# cougar_adapter.net
KiCad netlist of a schematic drawn in EAGLE
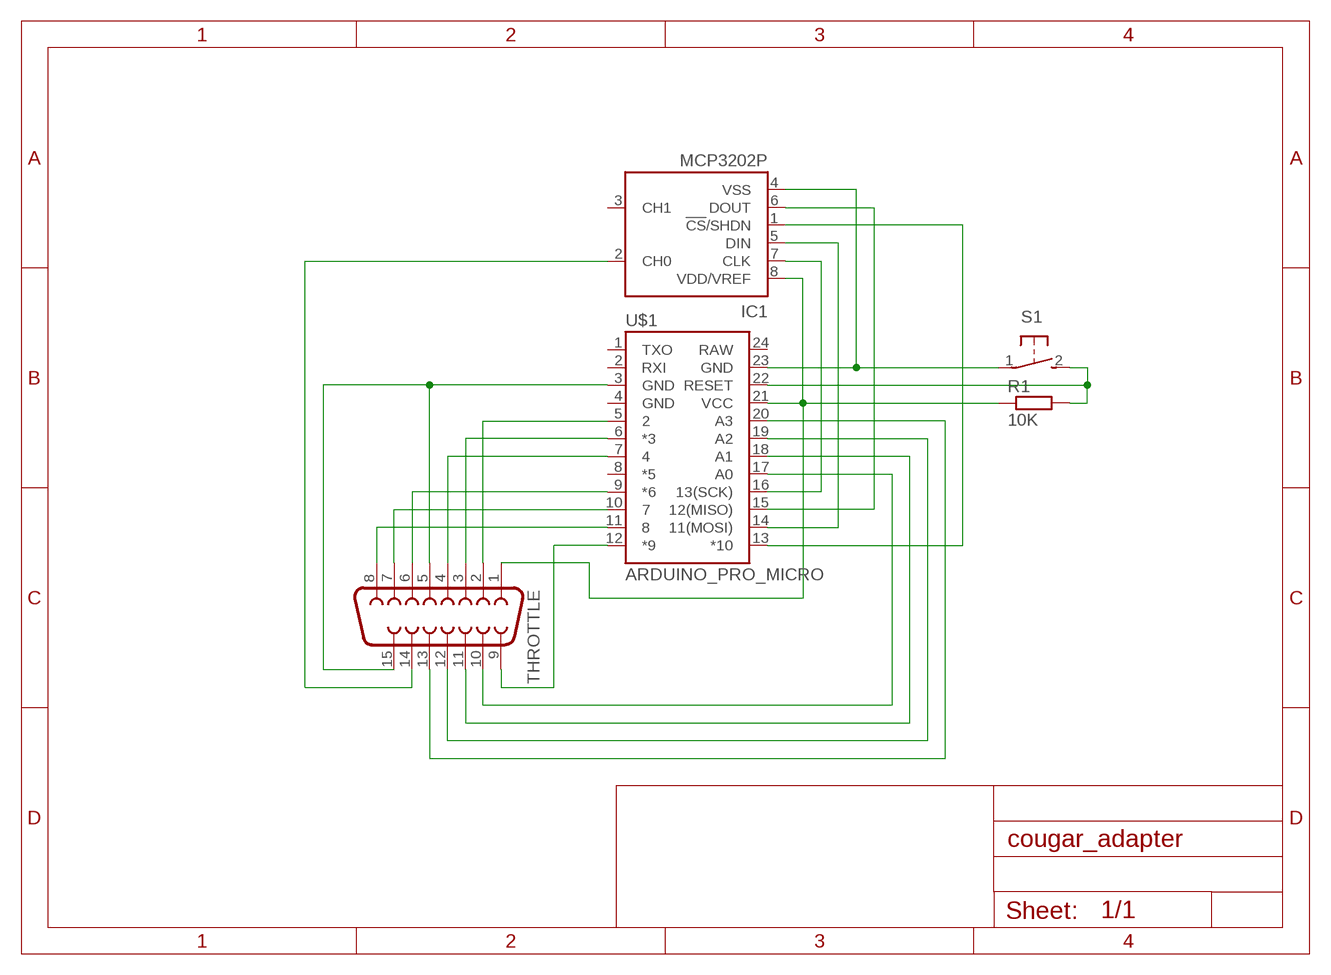
[diagram p0: schematic, sheet 1]

(export (version "E")
  (design (tool "Eeschema 10.0.6"))
  (components
    (comp (ref "IC1")
      (value "MCP3202P")
      (footprint "eagle-import:DIL8")
      (fields (field (name "MF") "MICROCHIP") (field (name "MPN") "MCP3202-CI/P"))
      (libsource (lib "eagle-import") (part "MCP3202P"))
    )
    (comp (ref "R1")
      (value "10K")
      (footprint "eagle-import:0204_7")
      (libsource (lib "eagle-import") (part "R-EU_0204/7"))
    )
    (comp (ref "S1")
      (value "31-XX")
      (footprint "eagle-import:B3F-31XX")
      (libsource (lib "eagle-import") (part "31-XX"))
    )
    (comp (ref "THROTTLE")
      (value "F15HDH")
      (footprint "eagle-import:HDF15H")
      (libsource (lib "eagle-import") (part "F15HDH"))
    )
    (comp (ref "U$1")
      (value "ARDUINO_PRO_MICRO")
      (footprint "eagle-import:ARDUINO_PRO_MICRO")
      (libsource (lib "eagle-import") (part "ARDUINO_PRO_MICRO"))
    )
  )
  (nets
    (net (code "1") (name "/GND") (class "Default")
      (node (ref "IC1") (pin "4") (pinfunction "VSS_4") (pintype "input"))
      (node (ref "S1") (pin "1") (pinfunction "P_1") (pintype "passive"))
      (node (ref "THROTTLE") (pin "15") (pinfunction "15_15") (pintype "passive"))
      (node (ref "THROTTLE") (pin "5") (pinfunction "5_5") (pintype "passive"))
      (node (ref "U$1") (pin "23") (pinfunction "GND_23") (pintype "bidirectional"))
      (node (ref "U$1") (pin "3") (pinfunction "GND_3") (pintype "bidirectional"))
    )
    (net (code "2") (name "Net-(IC1-CH0)") (class "Default")
      (node (ref "IC1") (pin "2") (pinfunction "CH0_2") (pintype "input"))
      (node (ref "THROTTLE") (pin "14") (pinfunction "14_14") (pintype "passive"))
    )
    (net (code "3") (name "Net-(IC1-CLK)") (class "Default")
      (node (ref "IC1") (pin "7") (pinfunction "CLK_7") (pintype "input"))
      (node (ref "U$1") (pin "16") (pinfunction "13(SCK)_16") (pintype "bidirectional"))
    )
    (net (code "4") (name "Net-(IC1-DIN)") (class "Default")
      (node (ref "IC1") (pin "5") (pinfunction "DIN_5") (pintype "input"))
      (node (ref "U$1") (pin "14") (pinfunction "11(MOSI)_14") (pintype "bidirectional"))
    )
    (net (code "5") (name "Net-(IC1-DOUT)") (class "Default")
      (node (ref "IC1") (pin "6") (pinfunction "DOUT_6") (pintype "input"))
      (node (ref "U$1") (pin "15") (pinfunction "12(MISO)_15") (pintype "bidirectional"))
    )
    (net (code "6") (name "Net-(IC1-VDD{slash}VREF)") (class "Default")
      (node (ref "IC1") (pin "8") (pinfunction "VDD/VREF_8") (pintype "input"))
      (node (ref "R1") (pin "1") (pinfunction "1_1") (pintype "passive"))
      (node (ref "THROTTLE") (pin "1") (pinfunction "1_1") (pintype "passive"))
      (node (ref "U$1") (pin "21") (pinfunction "VCC_21") (pintype "bidirectional"))
    )
    (net (code "7") (name "Net-(IC1-~{CS}{slash}SHDN)") (class "Default")
      (node (ref "IC1") (pin "1") (pinfunction "~{CS}/SHDN_1") (pintype "input"))
      (node (ref "U$1") (pin "13") (pinfunction "*10_13") (pintype "bidirectional"))
    )
    (net (code "8") (name "Net-(S1-S)") (class "Default")
      (node (ref "R1") (pin "2") (pinfunction "2_2") (pintype "passive"))
      (node (ref "S1") (pin "2") (pinfunction "S_2") (pintype "passive"))
      (node (ref "U$1") (pin "22") (pinfunction "RESET_22") (pintype "bidirectional"))
    )
    (net (code "9") (name "Net-(U$1-*3)") (class "Default")
      (node (ref "THROTTLE") (pin "3") (pinfunction "3_3") (pintype "passive"))
      (node (ref "U$1") (pin "6") (pinfunction "*3_6") (pintype "bidirectional"))
    )
    (net (code "10") (name "Net-(U$1-*6)") (class "Default")
      (node (ref "THROTTLE") (pin "6") (pinfunction "6_6") (pintype "passive"))
      (node (ref "U$1") (pin "9") (pinfunction "*6_9") (pintype "bidirectional"))
    )
    (net (code "11") (name "Net-(U$1-*9)") (class "Default")
      (node (ref "THROTTLE") (pin "9") (pinfunction "9_9") (pintype "passive"))
      (node (ref "U$1") (pin "12") (pinfunction "*9_12") (pintype "bidirectional"))
    )
    (net (code "12") (name "Net-(U$1-2)") (class "Default")
      (node (ref "THROTTLE") (pin "2") (pinfunction "2_2") (pintype "passive"))
      (node (ref "U$1") (pin "5") (pinfunction "2_5") (pintype "bidirectional"))
    )
    (net (code "13") (name "Net-(U$1-4)") (class "Default")
      (node (ref "THROTTLE") (pin "4") (pinfunction "4_4") (pintype "passive"))
      (node (ref "U$1") (pin "7") (pinfunction "4_7") (pintype "bidirectional"))
    )
    (net (code "14") (name "Net-(U$1-7)") (class "Default")
      (node (ref "THROTTLE") (pin "7") (pinfunction "7_7") (pintype "passive"))
      (node (ref "U$1") (pin "10") (pinfunction "7_10") (pintype "bidirectional"))
    )
    (net (code "15") (name "Net-(U$1-8)") (class "Default")
      (node (ref "THROTTLE") (pin "8") (pinfunction "8_8") (pintype "passive"))
      (node (ref "U$1") (pin "11") (pinfunction "8_11") (pintype "bidirectional"))
    )
    (net (code "16") (name "Net-(U$1-A0)") (class "Default")
      (node (ref "THROTTLE") (pin "10") (pinfunction "10_10") (pintype "passive"))
      (node (ref "U$1") (pin "17") (pinfunction "A0_17") (pintype "bidirectional"))
    )
    (net (code "17") (name "Net-(U$1-A1)") (class "Default")
      (node (ref "THROTTLE") (pin "11") (pinfunction "11_11") (pintype "passive"))
      (node (ref "U$1") (pin "18") (pinfunction "A1_18") (pintype "bidirectional"))
    )
    (net (code "18") (name "Net-(U$1-A2)") (class "Default")
      (node (ref "THROTTLE") (pin "12") (pinfunction "12_12") (pintype "passive"))
      (node (ref "U$1") (pin "19") (pinfunction "A2_19") (pintype "bidirectional"))
    )
    (net (code "19") (name "Net-(U$1-A3)") (class "Default")
      (node (ref "THROTTLE") (pin "13") (pinfunction "13_13") (pintype "passive"))
      (node (ref "U$1") (pin "20") (pinfunction "A3_20") (pintype "bidirectional"))
    )
    (net (code "20") (name "unconnected-(IC1-CH1-Pad3)") (class "Default")
      (node (ref "IC1") (pin "3") (pinfunction "CH1_3") (pintype "input"))
    )
    (net (code "21") (name "unconnected-(U$1-*5-Pad8)") (class "Default")
      (node (ref "U$1") (pin "8") (pinfunction "*5_8") (pintype "bidirectional"))
    )
    (net (code "22") (name "unconnected-(U$1-GND-Pad4)") (class "Default")
      (node (ref "U$1") (pin "4") (pinfunction "GND_4") (pintype "bidirectional"))
    )
    (net (code "23") (name "unconnected-(U$1-RAW-Pad24)") (class "Default")
      (node (ref "U$1") (pin "24") (pinfunction "RAW_24") (pintype "bidirectional"))
    )
    (net (code "24") (name "unconnected-(U$1-RXI-Pad2)") (class "Default")
      (node (ref "U$1") (pin "2") (pinfunction "RXI_2") (pintype "bidirectional"))
    )
    (net (code "25") (name "unconnected-(U$1-TXO-Pad1)") (class "Default")
      (node (ref "U$1") (pin "1") (pinfunction "TXO_1") (pintype "bidirectional"))
    )
  )
)
